# SH1_-_POWER.net
KiCad netlist of a schematic drawn in Altium Designer
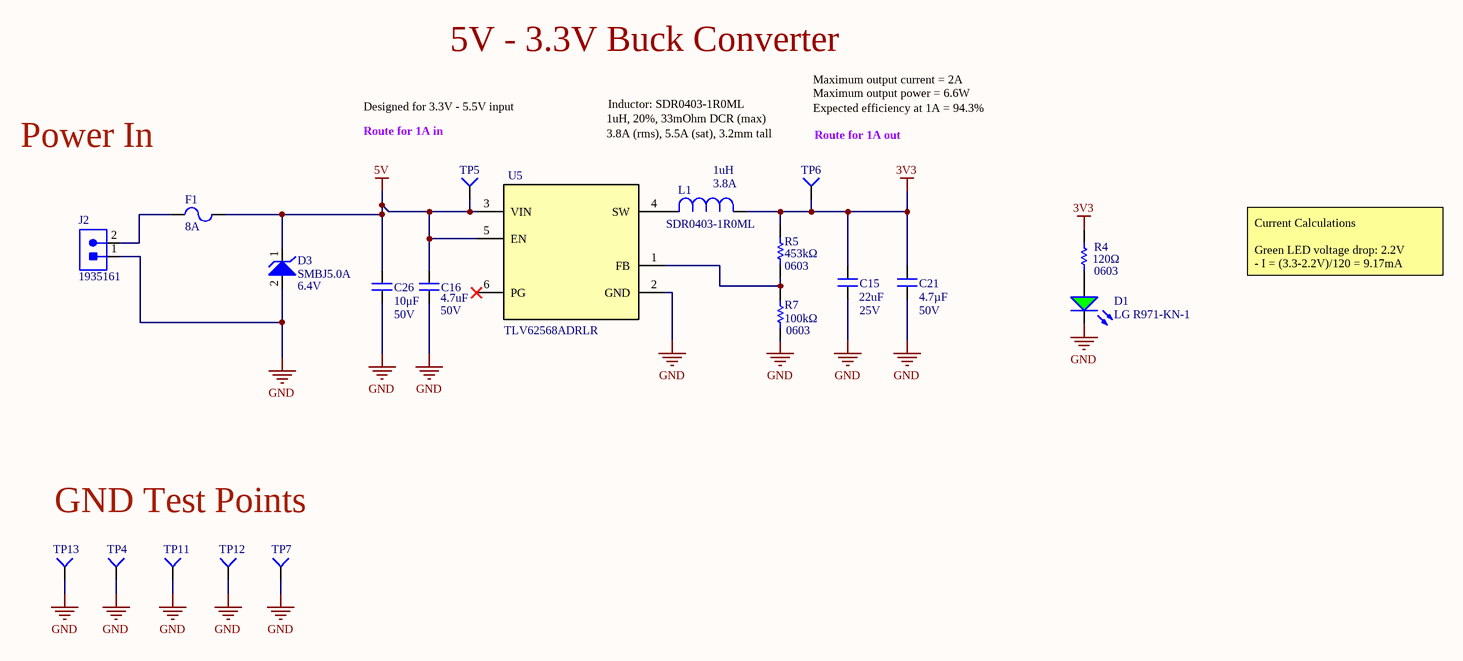
[diagram p0: SH1 - POWER.SchDoc]

(export (version "E")
  (design (tool "Eeschema 10.0.6"))
  (components
    (comp (ref "C15")
      (value "GRM32ER71E226ME15K")
      (footprint "CAPC3225X270N")
      (description "CAP CER 22UF 25V X7R 1210")
      (fields
        (field (name "TOLERANCE") "±20%")
        (field (name "VOLTAGE") "25V")
        (field (name "CAPACITANCE") "22uF")
      )
      (libsource (lib "UWRT_Schematic_Library_2020") (part "GRM32ER71E226ME15K"))
    )
    (comp (ref "C16")
      (value "4.7µF")
      (footprint "CAP1206")
      (description "CAP CER 4.7UF 50V X7R 1206")
      (fields
        (field (name "VOLTAGE RATING") "50V")
        (field (name "TOLERANCE") "10%")
        (field (name "CAPACITANCE") "4.7uF")
        (field (name "VOLTAGE") "50V")
      )
      (libsource (lib "UWRT_Schematic_Library_2020") (part "CAP_4.7µF_50V_1206"))
    )
    (comp (ref "C21")
      (value "4.7µF")
      (footprint "CAP1206")
      (description "CAP CER 4.7UF 50V X7R 1206")
      (fields (field (name "TOLERANCE") "10%") (field (name "VOLTAGE") "50V"))
      (libsource (lib "UWRT_Schematic_Library_2020") (part "CAP_4.7µF_50V_1206"))
    )
    (comp (ref "C26")
      (value "10μF")
      (footprint "CAP1206")
      (description "CAP CER 10UF 50V X5R 1206")
      (fields (field (name "VOLTAGE RATING") "50V") (field (name "Comment") "10uF"))
      (libsource (lib "UWRT_Schematic_Library_2020") (part "CAP_10uF_50V_1206"))
    )
    (comp (ref "D1")
      (value "LG R971-KN-1")
      (footprint "LED_0805_GREEN")
      (description "LED GREEN DIFFUSED 0805 SMD")
      (libsource (lib "UWRT_Schematic_Library_2020") (part "DIO_LED_G"))
    )
    (comp (ref "D3")
      (value "TVS_DIODE_UNIDIR_5V")
      (footprint "SMBJ5.0A")
      (description "TVS DIODE 5V 9.2V DO214AA")
      (fields
        (field (name "REVERSE BREAKDOWN VOLTAGE") "6.4V")
        (field (name "MANUFACTURER PART NUMBER 1") "SMBJ5.0A")
      )
      (libsource (lib "UWRT_Schematic_Library_2020") (part "TVS_DIODE_UNIDIR_5V"))
    )
    (comp (ref "F1")
      (value "FUSE_8A_1206")
      (footprint "FUSE_1206")
      (description "FUSE SMD 8A 24V")
      (fields (field (name "CURRENT RATING") "8A"))
      (libsource (lib "UWRT_Schematic_Library_2020") (part "FUSE_8A_1206"))
    )
    (comp (ref "J2")
      (value "1935161")
      (footprint "1935161")
      (description "TERM BLK 2POS SIDE ENTRY 5MM")
      (fields (field (name "VOLTAGE") "300V") (field (name "MANUFACTURER PART NUMBER 1") "1935161"))
      (libsource (lib "UWRT_Schematic_Library_2020") (part "CON_2M_TERM"))
    )
    (comp (ref "L1")
      (value "1uH")
      (footprint "IND_BOURNS_SDR04")
      (description "FIXED IND 1UH 3.8A 33 MOHM SMD")
      (fields
        (field (name "MANUFACTURER PART NUMBER 1") "SDR0403-1R0ML")
        (field (name "TOLERANCE") "±20%")
        (field (name "CURRENT RATING") "3.8A")
        (field (name "Comment") "IND_1uH_3.8A")
      )
      (libsource (lib "UWRT_Schematic_Library_2020") (part "IND_1uH_3.8A"))
    )
    (comp (ref "R4")
      (value "120Ω")
      (footprint "RESC0603(1608)_N")
      (description "RES 120 OHM 5% 1/10W 0603")
      (fields
        (field (name "TOLERANCE") "5%")
        (field (name "CASE CODE (IMPERIAL)") "0603")
        (field (name "Comment") "RES_120Ω_0603")
      )
      (libsource (lib "UWRT_Schematic_Library_2020") (part "RES_120Ω_0603_5%"))
    )
    (comp (ref "R5")
      (value "453kΩ")
      (footprint "RESC0603(1608)_N")
      (description "RES 453K OHM 1% 1/10W 0603")
      (fields
        (field (name "TOLERANCE") "1%")
        (field (name "CASE CODE (IMPERIAL)") "0603")
        (field (name "Comment") "RES_453kΩ_0603")
      )
      (libsource (lib "UWRT_Schematic_Library_2020") (part "RES_453kΩ_0603_1%"))
    )
    (comp (ref "R7")
      (value "100kΩ")
      (footprint "RESC0603(1608)_N")
      (description "RES 100K OHM 1% 1/10W 0603")
      (fields
        (field (name "TOLERANCE") "1%")
        (field (name "CASE CODE (IMPERIAL)") "0603")
        (field (name "Comment") "RES_100kΩ_0603_1%")
      )
      (libsource (lib "UWRT_Schematic_Library_2020") (part "RES_100kΩ_0603_1%"))
    )
    (comp (ref "TP4")
      (value "TESTPOINT_1MM_SQUARE")
      (footprint "TESTPOINT_SQUARE_1MM")
      (description "TESTPOINT 1MM SQUARE")
      (libsource (lib "UWRT_Schematic_Library_2020") (part "TESTPOINT_1MM_SQUARE"))
    )
    (comp (ref "TP5")
      (value "TESTPOINT_SMD_LOOP")
      (footprint "S1751-46R")
      (description "PC TEST POINT SMD")
      (libsource (lib "UWRT_Schematic_Library_2020") (part "TESTPOINT_SMD_LOOP"))
    )
    (comp (ref "TP6")
      (value "TESTPOINT_SMD_LOOP")
      (footprint "S1751-46R")
      (description "PC TEST POINT SMD")
      (libsource (lib "UWRT_Schematic_Library_2020") (part "TESTPOINT_SMD_LOOP"))
    )
    (comp (ref "TP7")
      (value "TESTPOINT_1MM_SQUARE")
      (footprint "TESTPOINT_SQUARE_1MM")
      (description "TESTPOINT 1MM SQUARE")
      (libsource (lib "UWRT_Schematic_Library_2020") (part "TESTPOINT_1MM_SQUARE"))
    )
    (comp (ref "TP11")
      (value "TESTPOINT_1MM_SQUARE")
      (footprint "TESTPOINT_SQUARE_1MM")
      (description "TESTPOINT 1MM SQUARE")
      (libsource (lib "UWRT_Schematic_Library_2020") (part "TESTPOINT_1MM_SQUARE"))
    )
    (comp (ref "TP12")
      (value "TESTPOINT_1MM_SQUARE")
      (footprint "TESTPOINT_SQUARE_1MM")
      (description "TESTPOINT 1MM SQUARE")
      (libsource (lib "UWRT_Schematic_Library_2020") (part "TESTPOINT_1MM_SQUARE"))
    )
    (comp (ref "TP13")
      (value "TESTPOINT_SMD_LOOP")
      (footprint "S1751-46R")
      (description "PC TEST POINT SMD")
      (libsource (lib "UWRT_Schematic_Library_2020") (part "TESTPOINT_SMD_LOOP"))
    )
    (comp (ref "U5")
      (value "TLV62568ADRLR")
      (footprint "SOT50P160X60-6N")
      (description "IC REG BUCK ADJUSTABLE 2A SOT563")
      (libsource (lib "UWRT_Schematic_Library_2020") (part "TLV62568ADRLR"))
    )
  )
  (nets
    (net (code "1") (name "3V3") (class "Default")
      (node (ref "C15") (pin "2") (pinfunction "2_2") (pintype "passive"))
      (node (ref "C21") (pin "2") (pinfunction "2_2") (pintype "passive"))
      (node (ref "L1") (pin "2") (pinfunction "2_2") (pintype "passive"))
      (node (ref "R4") (pin "2") (pinfunction "2_2") (pintype "passive"))
      (node (ref "R5") (pin "2") (pinfunction "2_2") (pintype "passive"))
      (node (ref "TP6") (pin "1") (pinfunction "=value_1") (pintype "passive"))
    )
    (net (code "2") (name "5V") (class "Default")
      (node (ref "C16") (pin "2") (pinfunction "2_2") (pintype "passive"))
      (node (ref "C26") (pin "2") (pinfunction "2_2") (pintype "passive"))
      (node (ref "D3") (pin "1") (pinfunction "1_1") (pintype "passive"))
      (node (ref "F1") (pin "2") (pinfunction "2_2") (pintype "passive"))
      (node (ref "TP5") (pin "1") (pinfunction "=value_1") (pintype "passive"))
      (node (ref "U5") (pin "3") (pinfunction "VIN_3") (pintype "power_in"))
      (node (ref "U5") (pin "5") (pinfunction "EN_5") (pintype "passive"))
    )
    (net (code "3") (name "GND") (class "Default")
      (node (ref "C15") (pin "1") (pinfunction "1_1") (pintype "passive"))
      (node (ref "C16") (pin "1") (pinfunction "1_1") (pintype "passive"))
      (node (ref "C21") (pin "1") (pinfunction "1_1") (pintype "passive"))
      (node (ref "C26") (pin "1") (pinfunction "1_1") (pintype "passive"))
      (node (ref "D1") (pin "2") (pinfunction "K_2") (pintype "passive"))
      (node (ref "D3") (pin "2") (pinfunction "2_2") (pintype "passive"))
      (node (ref "J2") (pin "1") (pinfunction "1_1") (pintype "passive"))
      (node (ref "R7") (pin "1") (pinfunction "1_1") (pintype "passive"))
      (node (ref "TP11") (pin "1") (pinfunction "=value_1") (pintype "passive"))
      (node (ref "TP12") (pin "1") (pinfunction "=value_1") (pintype "passive"))
      (node (ref "TP13") (pin "1") (pinfunction "=value_1") (pintype "passive"))
      (node (ref "TP4") (pin "1") (pinfunction "=value_1") (pintype "passive"))
      (node (ref "TP7") (pin "1") (pinfunction "=value_1") (pintype "passive"))
      (node (ref "U5") (pin "2") (pinfunction "GND_2") (pintype "power_in"))
    )
    (net (code "4") (name "Net-(D1-A)") (class "Default")
      (node (ref "D1") (pin "1") (pinfunction "A_1") (pintype "passive"))
      (node (ref "R4") (pin "1") (pinfunction "1_1") (pintype "passive"))
    )
    (net (code "5") (name "Net-(F1-Pad1)") (class "Default")
      (node (ref "F1") (pin "1") (pinfunction "1_1") (pintype "passive"))
      (node (ref "J2") (pin "2") (pinfunction "2_2") (pintype "passive"))
    )
    (net (code "6") (name "Net-(U5-FB)") (class "Default")
      (node (ref "R5") (pin "1") (pinfunction "1_1") (pintype "passive"))
      (node (ref "R7") (pin "2") (pinfunction "2_2") (pintype "passive"))
      (node (ref "U5") (pin "1") (pinfunction "FB_1") (pintype "passive"))
    )
    (net (code "7") (name "Net-(U5-SW)") (class "Default")
      (node (ref "L1") (pin "1") (pinfunction "1_1") (pintype "passive"))
      (node (ref "U5") (pin "4") (pinfunction "SW_4") (pintype "power_in"))
    )
    (net (code "8") (name "unconnected-(U5-PG-Pad6)") (class "Default")
      (node (ref "U5") (pin "6") (pinfunction "PG_6") (pintype "open_collector+no_connect"))
    )
  )
)
